# Communication_interfaces.net
KiCad netlist of a schematic drawn in Altium Designer
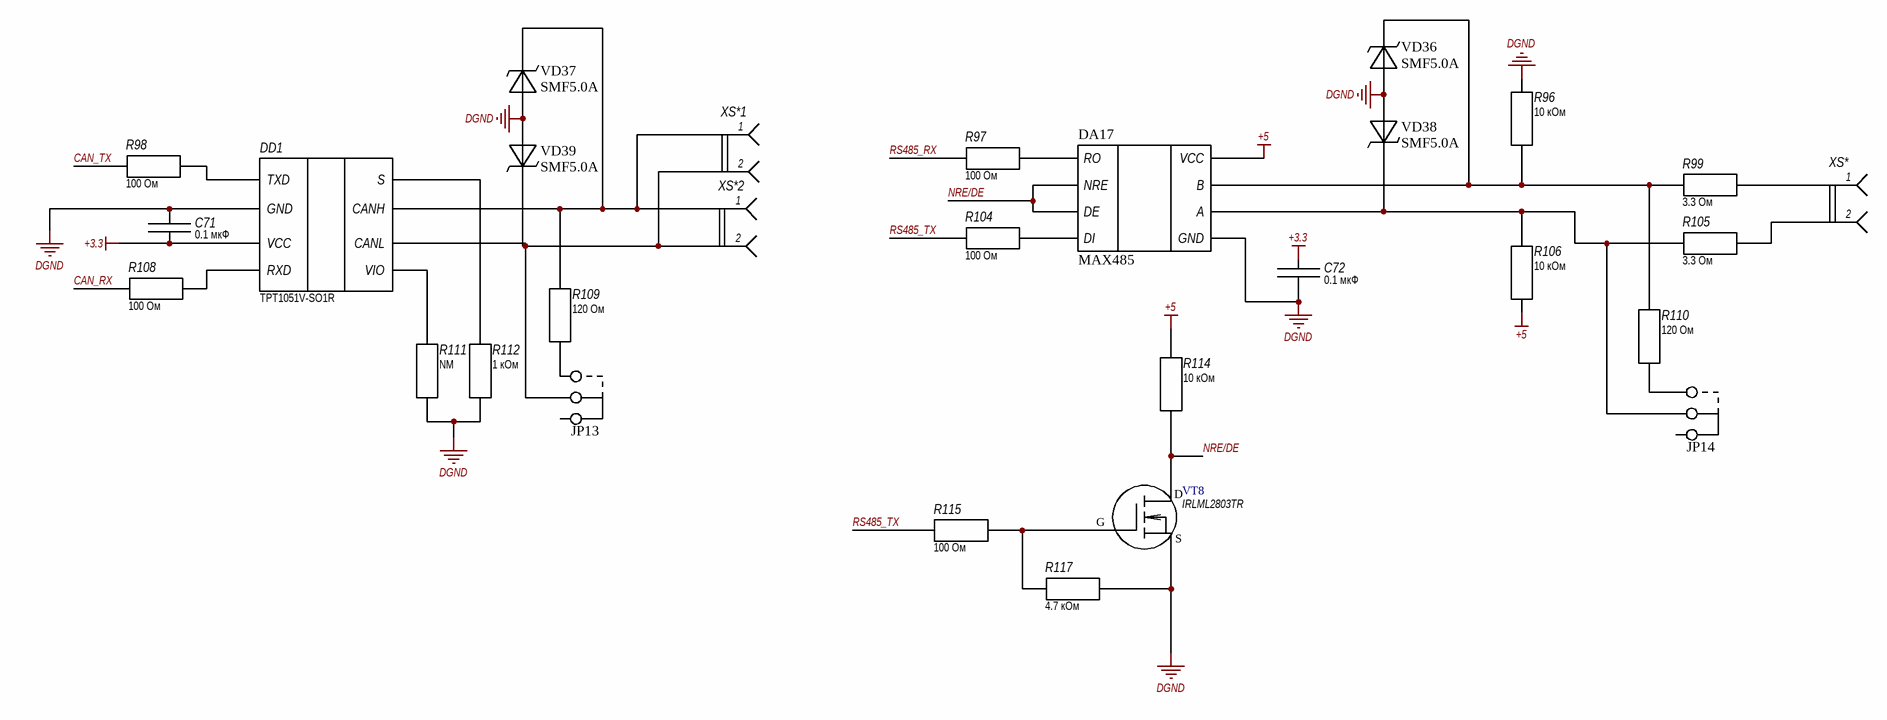
[diagram p0: Communication_interfaces.SchDoc]

(export (version "E")
  (design (tool "Eeschema 10.0.6"))
  (components
    (comp (ref "C71")
      (value "0.1 мкФ")
      (footprint "CC0603")
      (fields (field (name "VOLTAGE") "16В") (field (name "Comment") "Capacitor"))
      (libsource (lib "Main_components") (part "Capacitor"))
    )
    (comp (ref "C72")
      (value "0.1 мкФ")
      (footprint "CC0603")
      (fields (field (name "VOLTAGE") "16В") (field (name "Comment") "Capacitor"))
      (libsource (lib "Main_components") (part "Capacitor"))
    )
    (comp (ref "DA17")
      (value "MAX485")
      (footprint "SO8")
      (libsource (lib "Microcircuits") (part "MAX485ESA"))
    )
    (comp (ref "DD1")
      (value "TPT1051V-SO1R")
      (footprint "SO8")
      (description "Физический уровень CAN")
      (libsource (lib "Microcircuits") (part "TPT1051V-SO1R"))
    )
    (comp (ref "JP13") (value "Jumper") (footprint "PLS3") (libsource (lib "Connectors") (part "Jumper")))
    (comp (ref "JP14") (value "Jumper") (footprint "PLS3") (libsource (lib "Connectors") (part "Jumper")))
    (comp (ref "R96")
      (value "10 кОм")
      (footprint "RC0805")
      (fields (field (name "POWER") "125 мВт") (field (name "Comment") "Resistor"))
      (libsource (lib "Main_components") (part "Resistor"))
    )
    (comp (ref "R97")
      (value "100 Ом")
      (footprint "RC0603")
      (fields (field (name "POWER") "100 мВт") (field (name "Comment") "Resistor"))
      (libsource (lib "Main_components") (part "Resistor"))
    )
    (comp (ref "R98")
      (value "100 Ом")
      (footprint "RC0603")
      (fields (field (name "POWER") "100 мВт") (field (name "Comment") "Resistor"))
      (libsource (lib "Main_components") (part "Resistor"))
    )
    (comp (ref "R99")
      (value "3.3 Ом")
      (footprint "RC1206")
      (fields (field (name "POWER") "250 мВт") (field (name "Comment") "Resistor"))
      (libsource (lib "Main_components") (part "Resistor"))
    )
    (comp (ref "R104")
      (value "100 Ом")
      (footprint "RC0603")
      (fields (field (name "POWER") "100 мВт") (field (name "Comment") "Resistor"))
      (libsource (lib "Main_components") (part "Resistor"))
    )
    (comp (ref "R105")
      (value "3.3 Ом")
      (footprint "RC1206")
      (fields (field (name "POWER") "250 мВт") (field (name "Comment") "Resistor"))
      (libsource (lib "Main_components") (part "Resistor"))
    )
    (comp (ref "R106")
      (value "10 кОм")
      (footprint "RC0805")
      (fields (field (name "POWER") "125 мВт") (field (name "Comment") "Resistor"))
      (libsource (lib "Main_components") (part "Resistor"))
    )
    (comp (ref "R108")
      (value "100 Ом")
      (footprint "RC0603")
      (fields (field (name "POWER") "100 мВт") (field (name "Comment") "Resistor"))
      (libsource (lib "Main_components") (part "Resistor"))
    )
    (comp (ref "R109")
      (value "120 Ом")
      (footprint "RC1206")
      (fields (field (name "POWER") "250 мВт") (field (name "Comment") "Resistor"))
      (libsource (lib "Main_components") (part "Resistor"))
    )
    (comp (ref "R110")
      (value "120 Ом")
      (footprint "RC1206")
      (fields (field (name "POWER") "250 мВт") (field (name "Comment") "Resistor"))
      (libsource (lib "Main_components") (part "Resistor"))
    )
    (comp (ref "R111")
      (value "NM")
      (footprint "RC0603")
      (fields (field (name "POWER") "100 мВт") (field (name "Comment") "Resistor"))
      (libsource (lib "Main_components") (part "Resistor"))
    )
    (comp (ref "R112")
      (value "1 кОм")
      (footprint "RC0603")
      (fields (field (name "POWER") "100 мВт") (field (name "Comment") "Resistor"))
      (libsource (lib "Main_components") (part "Resistor"))
    )
    (comp (ref "R114")
      (value "10 кОм")
      (footprint "RC0805")
      (fields (field (name "POWER") "125 мВт") (field (name "Comment") "Resistor"))
      (libsource (lib "Main_components") (part "Resistor"))
    )
    (comp (ref "R115")
      (value "100 Ом")
      (footprint "RC0603")
      (fields (field (name "POWER") "100 мВт") (field (name "Comment") "Resistor"))
      (libsource (lib "Main_components") (part "Resistor"))
    )
    (comp (ref "R117")
      (value "4.7 кОм")
      (footprint "RC0603")
      (fields (field (name "POWER") "100 мВт") (field (name "Comment") "Resistor"))
      (libsource (lib "Main_components") (part "Resistor"))
    )
    (comp (ref "VD36")
      (value "SMF5.0A")
      (footprint "D0-124AC")
      (libsource (lib "Main_components") (part "TVS Diode"))
    )
    (comp (ref "VD37")
      (value "SMF5.0A")
      (footprint "D0-124AC")
      (libsource (lib "Main_components") (part "TVS Diode"))
    )
    (comp (ref "VD38")
      (value "SMF5.0A")
      (footprint "D0-124AC")
      (libsource (lib "Main_components") (part "TVS Diode"))
    )
    (comp (ref "VD39")
      (value "SMF5.0A")
      (footprint "D0-124AC")
      (libsource (lib "Main_components") (part "TVS Diode"))
    )
    (comp (ref "VT8")
      (value "IRLML2803TR")
      (footprint "SOT-23-3")
      (libsource (lib "Main_components") (part "N-MOSFET"))
    )
    (comp (ref "XS*")
      (value "DG141V-2.54-02P-14-00AH")
      (footprint "DG141V-2.54-02P")
      (libsource (lib "Connectors") (part "DG141V-2.54-02P-14-00AH"))
    )
    (comp (ref "XS*1")
      (value "DG141V-2.54-02P-14-00AH")
      (footprint "DG141V-2.54-02P")
      (libsource (lib "Connectors") (part "DG141V-2.54-02P-14-00AH"))
    )
    (comp (ref "XS*2")
      (value "DG141V-2.54-02P-14-00AH")
      (footprint "DG141V-2.54-02P")
      (libsource (lib "Connectors") (part "DG141V-2.54-02P-14-00AH"))
    )
  )
  (nets
    (net (code "1") (name "+3.3") (class "Default")
      (node (ref "C71") (pin "1") (pinfunction "1_1") (pintype "passive"))
      (node (ref "C72") (pin "2") (pinfunction "2_2") (pintype "passive"))
      (node (ref "DD1") (pin "3") (pinfunction "VCC_3") (pintype "passive"))
    )
    (net (code "2") (name "+5") (class "Default")
      (node (ref "DA17") (pin "5") (pinfunction "VCC_5") (pintype "passive"))
      (node (ref "R106") (pin "2") (pinfunction "2_2") (pintype "passive"))
      (node (ref "R114") (pin "1") (pinfunction "1_1") (pintype "passive"))
    )
    (net (code "3") (name "/CAN_RX") (class "Default")
      (node (ref "R108") (pin "2") (pinfunction "2_2") (pintype "passive"))
    )
    (net (code "4") (name "/CAN_TX") (class "Default")
      (node (ref "R98") (pin "2") (pinfunction "2_2") (pintype "passive"))
    )
    (net (code "5") (name "/NRE{slash}DE") (class "Default")
      (node (ref "DA17") (pin "2") (pinfunction "NRE_2") (pintype "passive"))
      (node (ref "DA17") (pin "3") (pinfunction "DE_3") (pintype "passive"))
      (node (ref "R114") (pin "2") (pinfunction "2_2") (pintype "passive"))
      (node (ref "VT8") (pin "D") (pinfunction "D_D") (pintype "passive"))
    )
    (net (code "6") (name "/RS485_RX") (class "Default")
      (node (ref "R97") (pin "2") (pinfunction "2_2") (pintype "passive"))
    )
    (net (code "7") (name "/RS485_TX") (class "Default")
      (node (ref "R104") (pin "2") (pinfunction "2_2") (pintype "passive"))
      (node (ref "R115") (pin "2") (pinfunction "2_2") (pintype "passive"))
    )
    (net (code "8") (name "DGND") (class "Default")
      (node (ref "C71") (pin "2") (pinfunction "2_2") (pintype "passive"))
      (node (ref "C72") (pin "1") (pinfunction "1_1") (pintype "passive"))
      (node (ref "DA17") (pin "8") (pinfunction "GND_8") (pintype "passive"))
      (node (ref "DD1") (pin "2") (pinfunction "GND_2") (pintype "passive"))
      (node (ref "R111") (pin "2") (pinfunction "2_2") (pintype "passive"))
      (node (ref "R112") (pin "2") (pinfunction "2_2") (pintype "passive"))
      (node (ref "R117") (pin "1") (pinfunction "1_1") (pintype "passive"))
      (node (ref "R96") (pin "1") (pinfunction "1_1") (pintype "passive"))
      (node (ref "VD36") (pin "A") (pinfunction "A_A") (pintype "passive"))
      (node (ref "VD37") (pin "A") (pinfunction "A_A") (pintype "passive"))
      (node (ref "VD38") (pin "A") (pinfunction "A_A") (pintype "passive"))
      (node (ref "VD39") (pin "A") (pinfunction "A_A") (pintype "passive"))
      (node (ref "VT8") (pin "S") (pinfunction "S_S") (pintype "passive"))
    )
    (net (code "9") (name "Net-(DA17-A)") (class "Default")
      (node (ref "DA17") (pin "7") (pinfunction "A_7") (pintype "passive"))
      (node (ref "JP14") (pin "2") (pinfunction "5_2") (pintype "passive"))
      (node (ref "R105") (pin "1") (pinfunction "1_1") (pintype "passive"))
      (node (ref "R106") (pin "1") (pinfunction "1_1") (pintype "passive"))
      (node (ref "VD38") (pin "C") (pinfunction "C_C") (pintype "passive"))
    )
    (net (code "10") (name "Net-(DA17-B)") (class "Default")
      (node (ref "DA17") (pin "6") (pinfunction "B_6") (pintype "passive"))
      (node (ref "R110") (pin "1") (pinfunction "1_1") (pintype "passive"))
      (node (ref "R96") (pin "2") (pinfunction "2_2") (pintype "passive"))
      (node (ref "R99") (pin "1") (pinfunction "1_1") (pintype "passive"))
      (node (ref "VD36") (pin "C") (pinfunction "C_C") (pintype "passive"))
    )
    (net (code "11") (name "Net-(DA17-DI)") (class "Default")
      (node (ref "DA17") (pin "4") (pinfunction "DI_4") (pintype "passive"))
      (node (ref "R104") (pin "1") (pinfunction "1_1") (pintype "passive"))
    )
    (net (code "12") (name "Net-(DA17-RO)") (class "Default")
      (node (ref "DA17") (pin "1") (pinfunction "RO_1") (pintype "passive"))
      (node (ref "R97") (pin "1") (pinfunction "1_1") (pintype "passive"))
    )
    (net (code "13") (name "Net-(DD1-CANH)") (class "Default")
      (node (ref "DD1") (pin "7") (pinfunction "CANH_7") (pintype "passive"))
      (node (ref "R109") (pin "1") (pinfunction "1_1") (pintype "passive"))
      (node (ref "VD37") (pin "C") (pinfunction "C_C") (pintype "passive"))
      (node (ref "XS*1") (pin "1") (pinfunction "1_1") (pintype "passive"))
      (node (ref "XS*2") (pin "1") (pinfunction "1_1") (pintype "passive"))
    )
    (net (code "14") (name "Net-(DD1-CANL)") (class "Default")
      (node (ref "DD1") (pin "6") (pinfunction "CANL_6") (pintype "passive"))
      (node (ref "JP13") (pin "2") (pinfunction "5_2") (pintype "passive"))
      (node (ref "VD39") (pin "C") (pinfunction "C_C") (pintype "passive"))
      (node (ref "XS*1") (pin "2") (pinfunction "2_2") (pintype "passive"))
      (node (ref "XS*2") (pin "2") (pinfunction "2_2") (pintype "passive"))
    )
    (net (code "15") (name "Net-(DD1-RXD)") (class "Default")
      (node (ref "DD1") (pin "4") (pinfunction "RXD_4") (pintype "passive"))
      (node (ref "R108") (pin "1") (pinfunction "1_1") (pintype "passive"))
    )
    (net (code "16") (name "Net-(DD1-S)") (class "Default")
      (node (ref "DD1") (pin "8") (pinfunction "S_8") (pintype "passive"))
      (node (ref "R112") (pin "1") (pinfunction "1_1") (pintype "passive"))
    )
    (net (code "17") (name "Net-(DD1-TXD)") (class "Default")
      (node (ref "DD1") (pin "1") (pinfunction "TXD_1") (pintype "passive"))
      (node (ref "R98") (pin "1") (pinfunction "1_1") (pintype "passive"))
    )
    (net (code "18") (name "Net-(DD1-VIO)") (class "Default")
      (node (ref "DD1") (pin "5") (pinfunction "VIO_5") (pintype "passive"))
      (node (ref "R111") (pin "1") (pinfunction "1_1") (pintype "passive"))
    )
    (net (code "19") (name "Net-(JP13-4)") (class "Default")
      (node (ref "JP13") (pin "1") (pinfunction "4_1") (pintype "passive"))
      (node (ref "R109") (pin "2") (pinfunction "2_2") (pintype "passive"))
    )
    (net (code "20") (name "Net-(JP14-4)") (class "Default")
      (node (ref "JP14") (pin "1") (pinfunction "4_1") (pintype "passive"))
      (node (ref "R110") (pin "2") (pinfunction "2_2") (pintype "passive"))
    )
    (net (code "21") (name "Net-(R99-Pad2)") (class "Default")
      (node (ref "R99") (pin "2") (pinfunction "2_2") (pintype "passive"))
      (node (ref "XS*") (pin "1") (pinfunction "1_1") (pintype "passive"))
    )
    (net (code "22") (name "Net-(R105-Pad2)") (class "Default")
      (node (ref "R105") (pin "2") (pinfunction "2_2") (pintype "passive"))
      (node (ref "XS*") (pin "2") (pinfunction "2_2") (pintype "passive"))
    )
    (net (code "23") (name "Net-(R115-Pad1)") (class "Default")
      (node (ref "R115") (pin "1") (pinfunction "1_1") (pintype "passive"))
      (node (ref "R117") (pin "2") (pinfunction "2_2") (pintype "passive"))
      (node (ref "VT8") (pin "G") (pinfunction "G_G") (pintype "passive"))
    )
    (net (code "24") (name "unconnected-(JP13-6-Pad3)") (class "Default")
      (node (ref "JP13") (pin "3") (pinfunction "6_3") (pintype "passive"))
    )
    (net (code "25") (name "unconnected-(JP14-6-Pad3)") (class "Default")
      (node (ref "JP14") (pin "3") (pinfunction "6_3") (pintype "passive"))
    )
  )
)
